# 464421_22-01_01_Sheet1.net
KiCad netlist of a schematic drawn in Altium Designer
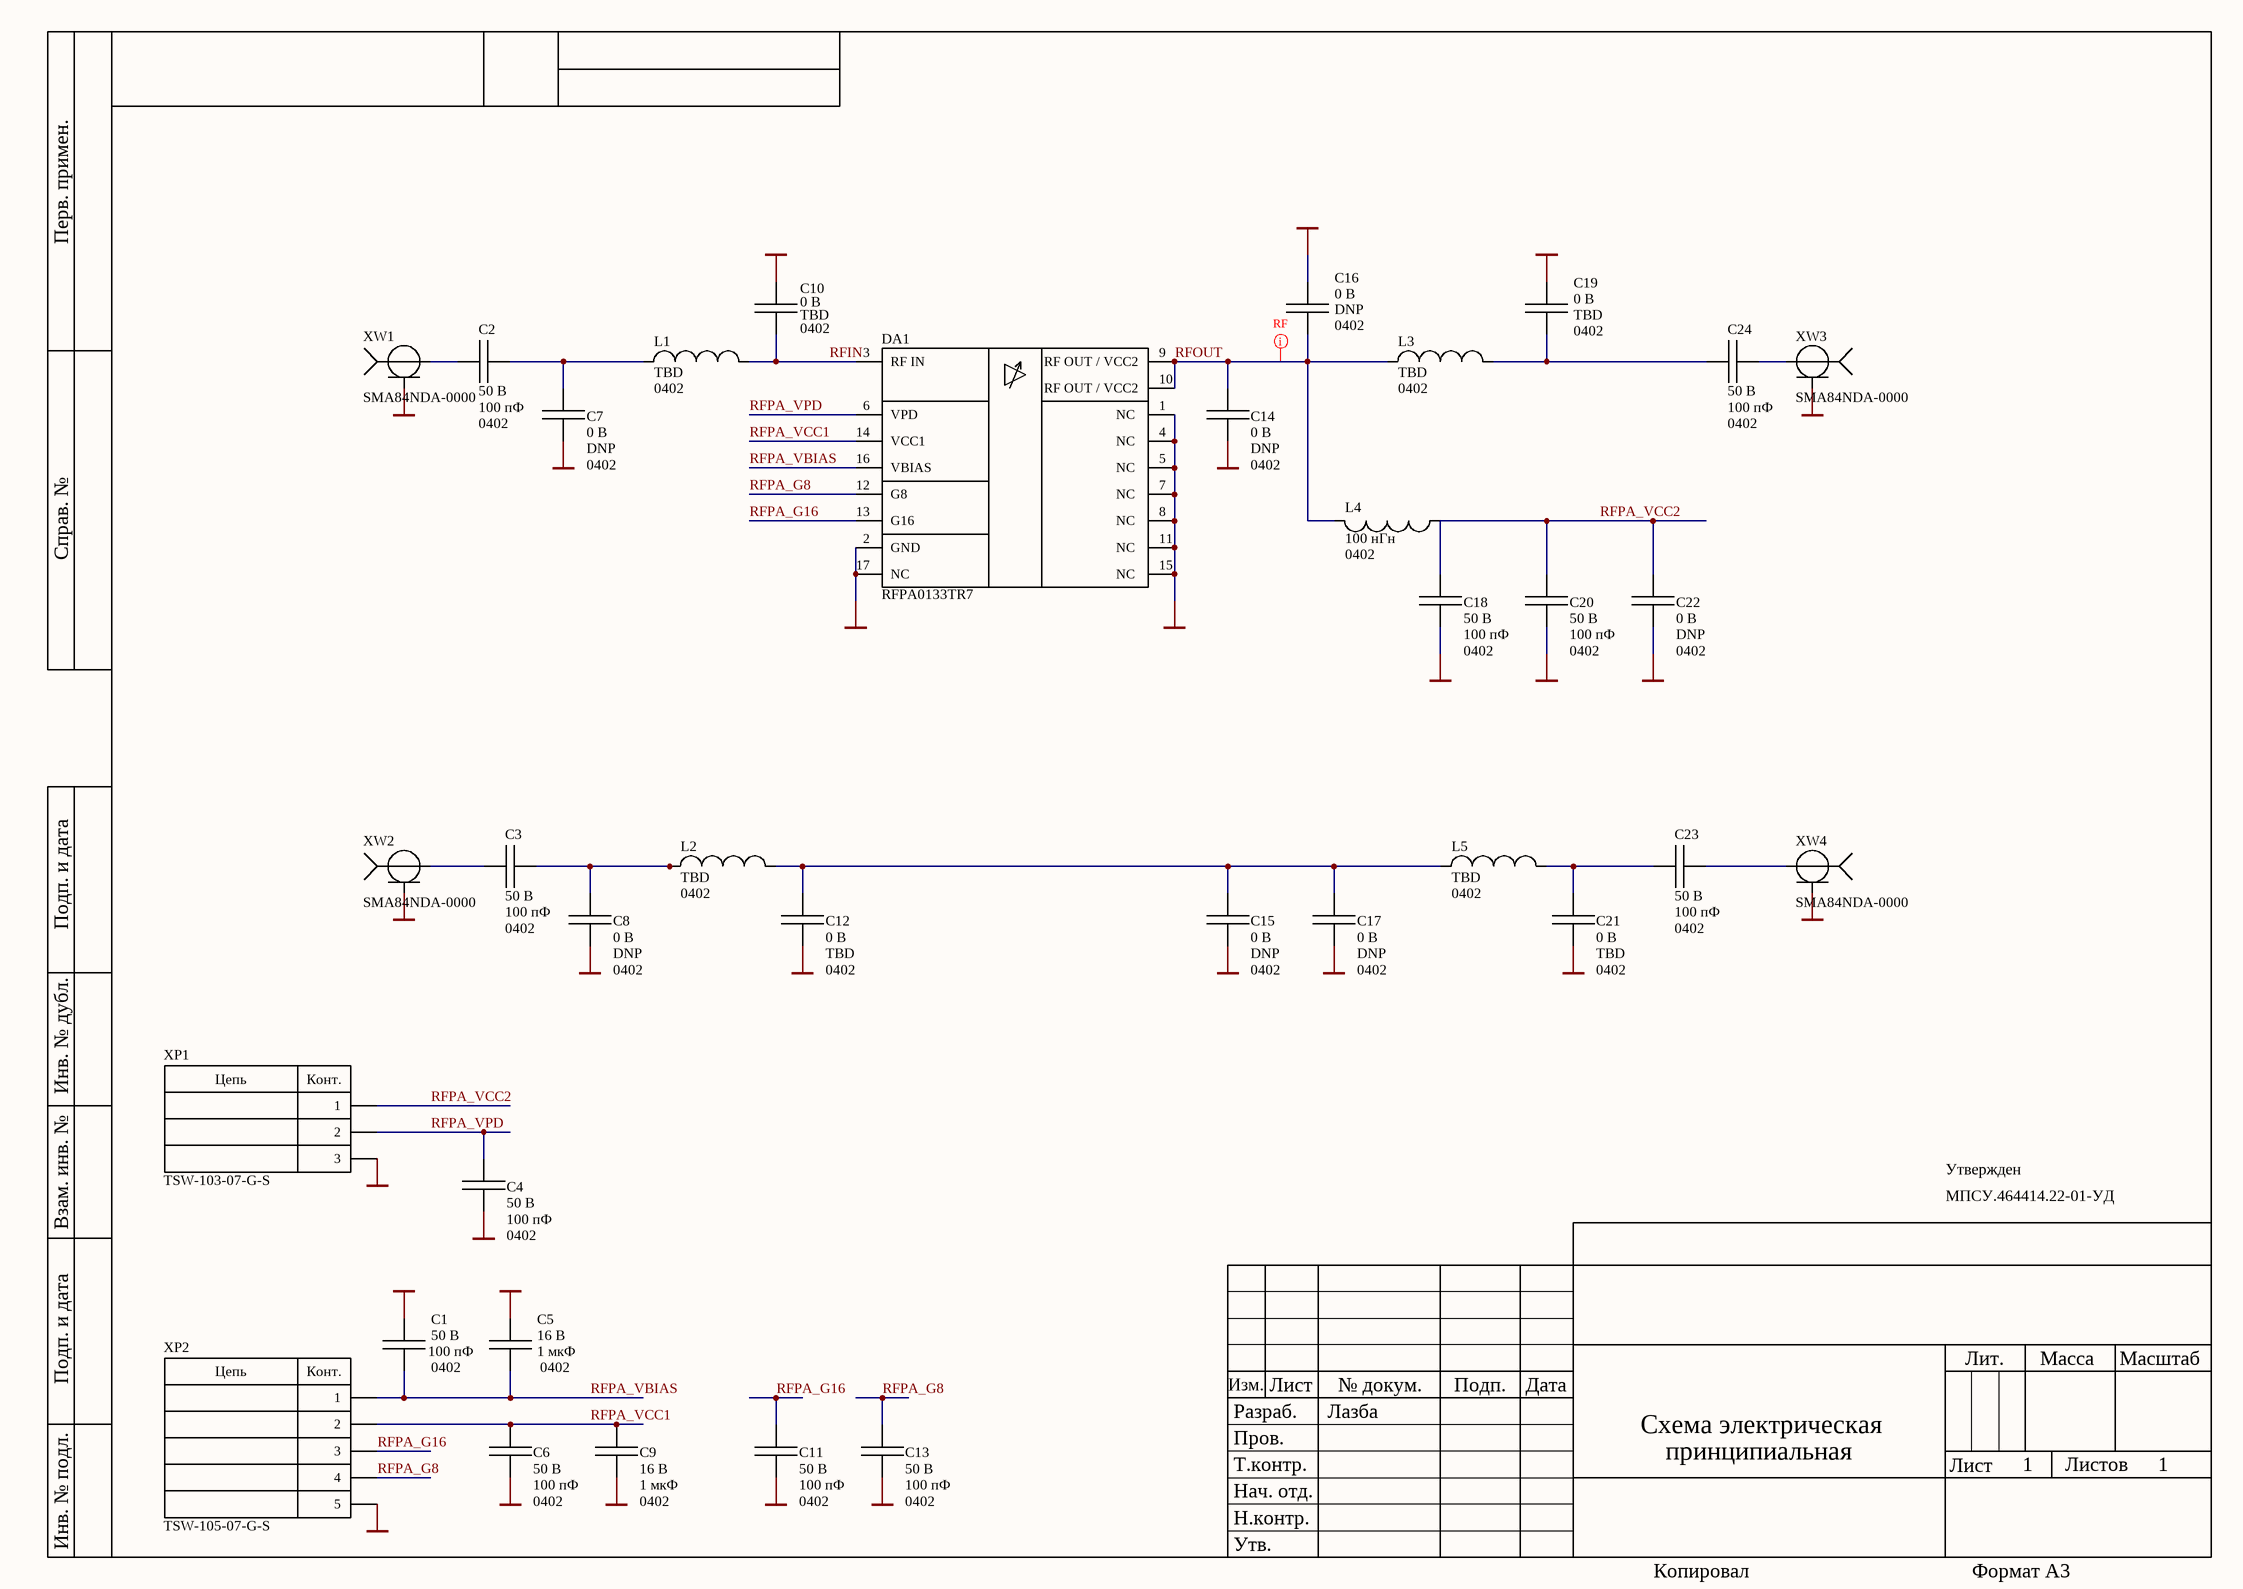
[diagram p0: МПСУ.464421.22-01.01 Sheet1.SchDoc]

(export (version "E")
  (design (tool "Eeschema 10.0.6"))
  (components
    (comp (ref "C1")
      (value "100 пФ")
      (footprint "Passive_V2_0:CAPC100X50X55L20N")
      (description "Capacitor 0402")
      (fields
        (field (name "PARTNUMBER") "GRM1555C1H101JZ01D")
        (field (name "MANUFACTURER") "Murata")
        (field (name "PEAK_CONDITION") "50 В")
        (field (name "PACKAGE") "0402")
        (field (name "DESIGNER") "Свидерский")
      )
      (libsource (lib "Passive_V2_0") (part "C 0402"))
    )
    (comp (ref "C2")
      (value "100 пФ")
      (footprint "Passive_V2_0:CAPC100X50X55L20N")
      (description "Capacitor 0402")
      (fields
        (field (name "PARTNUMBER") "GRM1555C1H101JZ01D")
        (field (name "MANUFACTURER") "Murata")
        (field (name "PEAK_CONDITION") "50 В")
        (field (name "PACKAGE") "0402")
        (field (name "DESIGNER") "Свидерский")
      )
      (libsource (lib "Passive_V2_0") (part "C 0402"))
    )
    (comp (ref "C3")
      (value "100 пФ")
      (footprint "Passive_V2_0:CAPC100X50X55L20N")
      (description "Capacitor 0402")
      (fields
        (field (name "PARTNUMBER") "GRM1555C1H101JZ01D")
        (field (name "MANUFACTURER") "Murata")
        (field (name "PEAK_CONDITION") "50 В")
        (field (name "PACKAGE") "0402")
        (field (name "DESIGNER") "Свидерский")
      )
      (libsource (lib "Passive_V2_0") (part "C 0402"))
    )
    (comp (ref "C4")
      (value "100 пФ")
      (footprint "Passive_V2_0:CAPC100X50X55L20N")
      (description "Capacitor 0402")
      (fields
        (field (name "PARTNUMBER") "GRM1555C1H101JZ01D")
        (field (name "MANUFACTURER") "Murata")
        (field (name "PEAK_CONDITION") "50 В")
        (field (name "PACKAGE") "0402")
        (field (name "DESIGNER") "Свидерский")
      )
      (libsource (lib "Passive_V2_0") (part "C 0402"))
    )
    (comp (ref "C5")
      (value "1 мкФ")
      (footprint "Passive_V2_0:CAPC100X50X55L20N")
      (description "Capacitor 0402")
      (fields
        (field (name "PARTNUMBER") "GRM155R61C105KA12D")
        (field (name "MANUFACTURER") "Murata")
        (field (name "PEAK_CONDITION") "16 В")
        (field (name "PACKAGE") "0402")
        (field (name "DESIGNER") "Свидерский")
      )
      (libsource (lib "Passive_V2_0") (part "C 0402"))
    )
    (comp (ref "C6")
      (value "100 пФ")
      (footprint "Passive_V2_0:CAPC100X50X55L20N")
      (description "Capacitor 0402")
      (fields
        (field (name "PARTNUMBER") "GRM1555C1H101JZ01D")
        (field (name "MANUFACTURER") "Murata")
        (field (name "PEAK_CONDITION") "50 В")
        (field (name "PACKAGE") "0402")
        (field (name "DESIGNER") "Свидерский")
      )
      (libsource (lib "Passive_V2_0") (part "C 0402"))
    )
    (comp (ref "C7")
      (value "DNP")
      (footprint "Passive_V2_0:CAPC100X50X55L20N")
      (description "Capacitor 0402")
      (fields
        (field (name "TOLERANCE") "0 %")
        (field (name "PEAK_CONDITION") "0 В")
        (field (name "PACKAGE") "0402")
        (field (name "Comment") "DNP 0402")
        (field (name "DESIGNER") "Свидерский")
      )
      (libsource (lib "Passive_V2_0") (part "C 0402"))
    )
    (comp (ref "C8")
      (value "DNP")
      (footprint "Passive_V2_0:CAPC100X50X55L20N")
      (description "Capacitor 0402")
      (fields
        (field (name "TOLERANCE") "0 %")
        (field (name "PEAK_CONDITION") "0 В")
        (field (name "PACKAGE") "0402")
        (field (name "Comment") "DNP 0402")
        (field (name "DESIGNER") "Свидерский")
      )
      (libsource (lib "Passive_V2_0") (part "C 0402"))
    )
    (comp (ref "C9")
      (value "1 мкФ")
      (footprint "Passive_V2_0:CAPC100X50X55L20N")
      (description "Capacitor 0402")
      (fields
        (field (name "PARTNUMBER") "GRM155R61C105KA12D")
        (field (name "MANUFACTURER") "Murata")
        (field (name "PEAK_CONDITION") "16 В")
        (field (name "PACKAGE") "0402")
        (field (name "DESIGNER") "Свидерский")
      )
      (libsource (lib "Passive_V2_0") (part "C 0402"))
    )
    (comp (ref "C10")
      (value "TBD")
      (footprint "Passive_V2_0:CAPC100X50X55L20N")
      (description "Capacitor 0402")
      (fields
        (field (name "TOLERANCE") "0 %")
        (field (name "PEAK_CONDITION") "0 В")
        (field (name "PACKAGE") "0402")
        (field (name "Comment") "TBD 0402")
        (field (name "DESIGNER") "Свидерский")
      )
      (libsource (lib "Passive_V2_0") (part "C 0402"))
    )
    (comp (ref "C11")
      (value "100 пФ")
      (footprint "Passive_V2_0:CAPC100X50X55L20N")
      (description "Capacitor 0402")
      (fields
        (field (name "PARTNUMBER") "GRM1555C1H101JZ01D")
        (field (name "MANUFACTURER") "Murata")
        (field (name "PEAK_CONDITION") "50 В")
        (field (name "PACKAGE") "0402")
        (field (name "DESIGNER") "Свидерский")
      )
      (libsource (lib "Passive_V2_0") (part "C 0402"))
    )
    (comp (ref "C12")
      (value "TBD")
      (footprint "Passive_V2_0:CAPC100X50X55L20N")
      (description "Capacitor 0402")
      (fields
        (field (name "TOLERANCE") "0 %")
        (field (name "PEAK_CONDITION") "0 В")
        (field (name "PACKAGE") "0402")
        (field (name "Comment") "TBD 0402")
        (field (name "DESIGNER") "Свидерский")
      )
      (libsource (lib "Passive_V2_0") (part "C 0402"))
    )
    (comp (ref "C13")
      (value "100 пФ")
      (footprint "Passive_V2_0:CAPC100X50X55L20N")
      (description "Capacitor 0402")
      (fields
        (field (name "PARTNUMBER") "GRM1555C1H101JZ01D")
        (field (name "MANUFACTURER") "Murata")
        (field (name "PEAK_CONDITION") "50 В")
        (field (name "PACKAGE") "0402")
        (field (name "DESIGNER") "Свидерский")
      )
      (libsource (lib "Passive_V2_0") (part "C 0402"))
    )
    (comp (ref "C14")
      (value "DNP")
      (footprint "Passive_V2_0:CAPC100X50X55L20N")
      (description "Capacitor 0402")
      (fields
        (field (name "TOLERANCE") "0 %")
        (field (name "PEAK_CONDITION") "0 В")
        (field (name "PACKAGE") "0402")
        (field (name "Comment") "DNP 0402")
        (field (name "DESIGNER") "Свидерский")
      )
      (libsource (lib "Passive_V2_0") (part "C 0402"))
    )
    (comp (ref "C15")
      (value "DNP")
      (footprint "Passive_V2_0:CAPC100X50X55L20N")
      (description "Capacitor 0402")
      (fields
        (field (name "TOLERANCE") "0 %")
        (field (name "PEAK_CONDITION") "0 В")
        (field (name "PACKAGE") "0402")
        (field (name "Comment") "DNP 0402")
        (field (name "DESIGNER") "Свидерский")
      )
      (libsource (lib "Passive_V2_0") (part "C 0402"))
    )
    (comp (ref "C16")
      (value "DNP")
      (footprint "Passive_V2_0:CAPC100X50X55L20N")
      (description "Capacitor 0402")
      (fields
        (field (name "TOLERANCE") "0 %")
        (field (name "PEAK_CONDITION") "0 В")
        (field (name "PACKAGE") "0402")
        (field (name "Comment") "DNP 0402")
        (field (name "DESIGNER") "Свидерский")
      )
      (libsource (lib "Passive_V2_0") (part "C 0402"))
    )
    (comp (ref "C17")
      (value "DNP")
      (footprint "Passive_V2_0:CAPC100X50X55L20N")
      (description "Capacitor 0402")
      (fields
        (field (name "TOLERANCE") "0 %")
        (field (name "PEAK_CONDITION") "0 В")
        (field (name "PACKAGE") "0402")
        (field (name "Comment") "DNP 0402")
        (field (name "DESIGNER") "Свидерский")
      )
      (libsource (lib "Passive_V2_0") (part "C 0402"))
    )
    (comp (ref "C18")
      (value "100 пФ")
      (footprint "Passive_V2_0:CAPC100X50X55L20N")
      (description "Capacitor 0402")
      (fields
        (field (name "PARTNUMBER") "GRM1555C1H101JZ01D")
        (field (name "MANUFACTURER") "Murata")
        (field (name "PEAK_CONDITION") "50 В")
        (field (name "PACKAGE") "0402")
        (field (name "DESIGNER") "Свидерский")
      )
      (libsource (lib "Passive_V2_0") (part "C 0402"))
    )
    (comp (ref "C19")
      (value "TBD")
      (footprint "Passive_V2_0:CAPC100X50X55L20N")
      (description "Capacitor 0402")
      (fields
        (field (name "TOLERANCE") "0 %")
        (field (name "PEAK_CONDITION") "0 В")
        (field (name "PACKAGE") "0402")
        (field (name "Comment") "TBD 0402")
        (field (name "DESIGNER") "Свидерский")
      )
      (libsource (lib "Passive_V2_0") (part "C 0402"))
    )
    (comp (ref "C20")
      (value "100 пФ")
      (footprint "Passive_V2_0:CAPC100X50X55L20N")
      (description "Capacitor 0402")
      (fields
        (field (name "PARTNUMBER") "GRM1555C1H101JZ01D")
        (field (name "MANUFACTURER") "Murata")
        (field (name "PEAK_CONDITION") "50 В")
        (field (name "PACKAGE") "0402")
        (field (name "DESIGNER") "Свидерский")
      )
      (libsource (lib "Passive_V2_0") (part "C 0402"))
    )
    (comp (ref "C21")
      (value "TBD")
      (footprint "Passive_V2_0:CAPC100X50X55L20N")
      (description "Capacitor 0402")
      (fields
        (field (name "TOLERANCE") "0 %")
        (field (name "PEAK_CONDITION") "0 В")
        (field (name "PACKAGE") "0402")
        (field (name "Comment") "TBD 0402")
        (field (name "DESIGNER") "Свидерский")
      )
      (libsource (lib "Passive_V2_0") (part "C 0402"))
    )
    (comp (ref "C22")
      (value "DNP")
      (footprint "Passive_V2_0:CAPC100X50X55L20N")
      (description "Capacitor 0402")
      (fields
        (field (name "TOLERANCE") "0 %")
        (field (name "PEAK_CONDITION") "0 В")
        (field (name "PACKAGE") "0402")
        (field (name "Comment") "DNP 0402")
        (field (name "DESIGNER") "Свидерский")
      )
      (libsource (lib "Passive_V2_0") (part "C 0402"))
    )
    (comp (ref "C23")
      (value "100 пФ")
      (footprint "Passive_V2_0:CAPC100X50X55L20N")
      (description "Capacitor 0402")
      (fields
        (field (name "PARTNUMBER") "GRM1555C1H101JZ01D")
        (field (name "MANUFACTURER") "Murata")
        (field (name "PEAK_CONDITION") "50 В")
        (field (name "PACKAGE") "0402")
        (field (name "DESIGNER") "Свидерский")
      )
      (libsource (lib "Passive_V2_0") (part "C 0402"))
    )
    (comp (ref "C24")
      (value "100 пФ")
      (footprint "Passive_V2_0:CAPC100X50X55L20N")
      (description "Capacitor 0402")
      (fields
        (field (name "PARTNUMBER") "GRM1555C1H101JZ01D")
        (field (name "MANUFACTURER") "Murata")
        (field (name "PEAK_CONDITION") "50 В")
        (field (name "PACKAGE") "0402")
        (field (name "DESIGNER") "Свидерский")
      )
      (libsource (lib "Passive_V2_0") (part "C 0402"))
    )
    (comp (ref "DA1")
      (value "RFPA0133TR7")
      (footprint "IC_V2_0:QFN50P300X300X90_HS-17N")
      (description "380 to 960 MHz, 3 to 5V programmable gain high efficiency power amplifier")
      (fields
        (field (name "MANUFACTURER") "RFD, Qorvo")
        (field (name "PARTNUMBER") "RFPA0133TR7")
        (field (name "DESIGNER") "Лазба")
      )
      (libsource (lib "IC_V2_0") (part "RFPA0133TR7"))
    )
    (comp (ref "L1")
      (value "TBD")
      (footprint "Passive_V2_0:INDC100X50X60L10N")
      (description "Inductor 0402")
      (fields
        (field (name "TOLERANCE") "0 %")
        (field (name "PACKAGE") "0402")
        (field (name "Comment") "TBD 0402")
        (field (name "DESIGNER") "Свидерский")
      )
      (libsource (lib "Passive_V2_0") (part "L 0402"))
    )
    (comp (ref "L2")
      (value "TBD")
      (footprint "Passive_V2_0:INDC100X50X60L10N")
      (description "Inductor 0402")
      (fields
        (field (name "TOLERANCE") "0 %")
        (field (name "PACKAGE") "0402")
        (field (name "Comment") "TBD 0402")
        (field (name "DESIGNER") "Свидерский")
      )
      (libsource (lib "Passive_V2_0") (part "L 0402"))
    )
    (comp (ref "L3")
      (value "TBD")
      (footprint "Passive_V2_0:INDC100X50X60L10N")
      (description "Inductor 0402")
      (fields
        (field (name "TOLERANCE") "0 %")
        (field (name "PACKAGE") "0402")
        (field (name "Comment") "TBD 0402")
        (field (name "DESIGNER") "Свидерский")
      )
      (libsource (lib "Passive_V2_0") (part "L 0402"))
    )
    (comp (ref "L4")
      (value "100 нГн")
      (footprint "Passive_V2_0:INDC100X50X60L10N")
      (description "Inductor 0402")
      (fields
        (field (name "PARTNUMBER") "LQG15HNR10J02D")
        (field (name "TOLERANCE") "5 %")
        (field (name "PACKAGE") "0402")
        (field (name "DESIGNER") "Свидерский")
      )
      (libsource (lib "Passive_V2_0") (part "L 0402"))
    )
    (comp (ref "L5")
      (value "TBD")
      (footprint "Passive_V2_0:INDC100X50X60L10N")
      (description "Inductor 0402")
      (fields
        (field (name "TOLERANCE") "0 %")
        (field (name "PACKAGE") "0402")
        (field (name "Comment") "TBD 0402")
        (field (name "DESIGNER") "Свидерский")
      )
      (libsource (lib "Passive_V2_0") (part "L 0402"))
    )
    (comp (ref "XP1")
      (value "TSW-103-07-G-S")
      (footprint "Connectors_V2_0:TSW-103-07-G-S")
      (description "Вилка 2,54 мм")
      (fields
        (field (name "MANUFACTURER") "Samtec")
        (field (name "PARTNUMBER") "TSW-103-07-G-S")
        (field (name "DESIGNER") "Затонская")
      )
      (libsource (lib "Connectors_V2_0") (part "TSW-103-07-G-S"))
    )
    (comp (ref "XP2")
      (value "TSW-105-07-G-S")
      (footprint "Connectors_V2_0:TSW-105-07-G-S")
      (description "Вилка 2,54 мм")
      (fields
        (field (name "MANUFACTURER") "Samtec")
        (field (name "PARTNUMBER") "TSW-105-07-G-S")
        (field (name "DESIGNER") "Затонская")
      )
      (libsource (lib "Connectors_V2_0") (part "TSW-105-07-G-S"))
    )
    (comp (ref "XW1")
      (value "SMA84NDA-0000")
      (footprint "Connectors_V2_0:SMA84NDA-0000")
      (description "SMA Jack P.C.B Mount (End Launch) 50 Ohm")
      (fields
        (field (name "MANUFACTURER") "Jyebao")
        (field (name "PARTNUMBER") "SMA84NDA-0000")
        (field (name "DESIGNER") "Карпов")
      )
      (libsource (lib "Connectors_V2_0") (part "SMA84NDA-0000"))
    )
    (comp (ref "XW2")
      (value "SMA84NDA-0000")
      (footprint "Connectors_V2_0:SMA84NDA-0000")
      (description "SMA Jack P.C.B Mount (End Launch) 50 Ohm")
      (fields
        (field (name "MANUFACTURER") "Jyebao")
        (field (name "PARTNUMBER") "SMA84NDA-0000")
        (field (name "DESIGNER") "Карпов")
      )
      (libsource (lib "Connectors_V2_0") (part "SMA84NDA-0000"))
    )
    (comp (ref "XW3")
      (value "SMA84NDA-0000")
      (footprint "Connectors_V2_0:SMA84NDA-0000")
      (description "SMA Jack P.C.B Mount (End Launch) 50 Ohm")
      (fields
        (field (name "MANUFACTURER") "Jyebao")
        (field (name "PARTNUMBER") "SMA84NDA-0000")
        (field (name "DESIGNER") "Карпов")
      )
      (libsource (lib "Connectors_V2_0") (part "SMA84NDA-0000"))
    )
    (comp (ref "XW4")
      (value "SMA84NDA-0000")
      (footprint "Connectors_V2_0:SMA84NDA-0000")
      (description "SMA Jack P.C.B Mount (End Launch) 50 Ohm")
      (fields
        (field (name "MANUFACTURER") "Jyebao")
        (field (name "PARTNUMBER") "SMA84NDA-0000")
        (field (name "DESIGNER") "Карпов")
      )
      (libsource (lib "Connectors_V2_0") (part "SMA84NDA-0000"))
    )
  )
  (nets
    (net (code "2") (name "/RFIN") (class "Default")
      (node (ref "C10") (pin "1") (pinfunction "1_1") (pintype "passive"))
      (node (ref "DA1") (pin "3") (pinfunction "RF_IN_3") (pintype "passive"))
      (node (ref "L1") (pin "2") (pinfunction "2_2") (pintype "passive"))
    )
    (net (code "3") (name "/RFOUT") (class "Default")
      (node (ref "C14") (pin "1") (pinfunction "1_1") (pintype "passive"))
      (node (ref "C16") (pin "2") (pinfunction "2_2") (pintype "passive"))
      (node (ref "DA1") (pin "10") (pinfunction "RF_OUT_/_VCC2_10") (pintype "passive"))
      (node (ref "DA1") (pin "9") (pinfunction "RF_OUT_/_VCC2_9") (pintype "passive"))
      (node (ref "L3") (pin "1") (pinfunction "1_1") (pintype "passive"))
      (node (ref "L4") (pin "2") (pinfunction "2_2") (pintype "passive"))
    )
    (net (code "4") (name "/RFPA_G8") (class "Default")
      (node (ref "C13") (pin "2") (pinfunction "2_2") (pintype "passive"))
      (node (ref "DA1") (pin "12") (pinfunction "G8_12") (pintype "passive"))
      (node (ref "XP2") (pin "4") (pinfunction "4_4") (pintype "passive"))
    )
    (net (code "5") (name "/RFPA_G16") (class "Default")
      (node (ref "C11") (pin "2") (pinfunction "2_2") (pintype "passive"))
      (node (ref "DA1") (pin "13") (pinfunction "G16_13") (pintype "passive"))
      (node (ref "XP2") (pin "3") (pinfunction "3_3") (pintype "passive"))
    )
    (net (code "6") (name "/RFPA_VBIAS") (class "Default")
      (node (ref "C1") (pin "2") (pinfunction "2_2") (pintype "passive"))
      (node (ref "C5") (pin "2") (pinfunction "2_2") (pintype "passive"))
      (node (ref "DA1") (pin "16") (pinfunction "VBIAS_16") (pintype "passive"))
      (node (ref "XP2") (pin "1") (pinfunction "1_1") (pintype "passive"))
    )
    (net (code "7") (name "/RFPA_VCC2") (class "Default")
      (node (ref "C18") (pin "1") (pinfunction "1_1") (pintype "passive"))
      (node (ref "C20") (pin "1") (pinfunction "1_1") (pintype "passive"))
      (node (ref "C22") (pin "1") (pinfunction "1_1") (pintype "passive"))
      (node (ref "L4") (pin "1") (pinfunction "1_1") (pintype "passive"))
      (node (ref "XP1") (pin "1") (pinfunction "1_1") (pintype "passive"))
    )
    (net (code "8") (name "/RFPA_VPD") (class "Default")
      (node (ref "C4") (pin "2") (pinfunction "2_2") (pintype "passive"))
      (node (ref "DA1") (pin "6") (pinfunction "VPD_6") (pintype "passive"))
      (node (ref "XP1") (pin "2") (pinfunction "2_2") (pintype "passive"))
    )
    (net (code "9") (name "/RFPA_VСС1") (class "Default")
      (node (ref "C6") (pin "2") (pinfunction "2_2") (pintype "passive"))
      (node (ref "C9") (pin "2") (pinfunction "2_2") (pintype "passive"))
      (node (ref "DA1") (pin "14") (pinfunction "VCC1_14") (pintype "passive"))
      (node (ref "XP2") (pin "2") (pinfunction "2_2") (pintype "passive"))
    )
    (net (code "10") (name "GND") (class "Default")
      (node (ref "C1") (pin "1") (pinfunction "1_1") (pintype "passive"))
      (node (ref "C10") (pin "2") (pinfunction "2_2") (pintype "passive"))
      (node (ref "C11") (pin "1") (pinfunction "1_1") (pintype "passive"))
      (node (ref "C12") (pin "2") (pinfunction "2_2") (pintype "passive"))
      (node (ref "C13") (pin "1") (pinfunction "1_1") (pintype "passive"))
      (node (ref "C14") (pin "2") (pinfunction "2_2") (pintype "passive"))
      (node (ref "C15") (pin "1") (pinfunction "1_1") (pintype "passive"))
      (node (ref "C16") (pin "1") (pinfunction "1_1") (pintype "passive"))
      (node (ref "C17") (pin "2") (pinfunction "2_2") (pintype "passive"))
      (node (ref "C18") (pin "2") (pinfunction "2_2") (pintype "passive"))
      (node (ref "C19") (pin "2") (pinfunction "2_2") (pintype "passive"))
      (node (ref "C20") (pin "2") (pinfunction "2_2") (pintype "passive"))
      (node (ref "C21") (pin "2") (pinfunction "2_2") (pintype "passive"))
      (node (ref "C22") (pin "2") (pinfunction "2_2") (pintype "passive"))
      (node (ref "C4") (pin "1") (pinfunction "1_1") (pintype "passive"))
      (node (ref "C5") (pin "1") (pinfunction "1_1") (pintype "passive"))
      (node (ref "C6") (pin "1") (pinfunction "1_1") (pintype "passive"))
      (node (ref "C7") (pin "2") (pinfunction "2_2") (pintype "passive"))
      (node (ref "C8") (pin "2") (pinfunction "2_2") (pintype "passive"))
      (node (ref "C9") (pin "1") (pinfunction "1_1") (pintype "passive"))
      (node (ref "DA1") (pin "1") (pinfunction "NC_1") (pintype "passive"))
      (node (ref "DA1") (pin "11") (pinfunction "NC_11") (pintype "passive"))
      (node (ref "DA1") (pin "15") (pinfunction "NC_15") (pintype "passive"))
      (node (ref "DA1") (pin "17") (pinfunction "NC_17") (pintype "passive"))
      (node (ref "DA1") (pin "2") (pinfunction "GND_2") (pintype "passive"))
      (node (ref "DA1") (pin "4") (pinfunction "NC_4") (pintype "passive"))
      (node (ref "DA1") (pin "5") (pinfunction "NC_5") (pintype "passive"))
      (node (ref "DA1") (pin "7") (pinfunction "NC_7") (pintype "passive"))
      (node (ref "DA1") (pin "8") (pinfunction "NC_8") (pintype "passive"))
      (node (ref "XP1") (pin "3") (pinfunction "3_3") (pintype "passive"))
      (node (ref "XP2") (pin "5") (pinfunction "5_5") (pintype "passive"))
      (node (ref "XW1") (pin "2") (pinfunction "GND_2") (pintype "passive"))
      (node (ref "XW2") (pin "2") (pinfunction "GND_2") (pintype "passive"))
      (node (ref "XW3") (pin "2") (pinfunction "GND_2") (pintype "passive"))
      (node (ref "XW4") (pin "2") (pinfunction "GND_2") (pintype "passive"))
    )
    (net (code "11") (name "Net-(C2-Pad2)") (class "Default")
      (node (ref "C2") (pin "2") (pinfunction "2_2") (pintype "passive"))
      (node (ref "C7") (pin "1") (pinfunction "1_1") (pintype "passive"))
      (node (ref "L1") (pin "1") (pinfunction "1_1") (pintype "passive"))
    )
    (net (code "12") (name "Net-(C3-Pad2)") (class "Default")
      (node (ref "C3") (pin "2") (pinfunction "2_2") (pintype "passive"))
      (node (ref "C8") (pin "1") (pinfunction "1_1") (pintype "passive"))
      (node (ref "L2") (pin "1") (pinfunction "1_1") (pintype "passive"))
    )
    (net (code "13") (name "Net-(C12-Pad1)") (class "Default")
      (node (ref "C12") (pin "1") (pinfunction "1_1") (pintype "passive"))
      (node (ref "C15") (pin "2") (pinfunction "2_2") (pintype "passive"))
      (node (ref "C17") (pin "1") (pinfunction "1_1") (pintype "passive"))
      (node (ref "L2") (pin "2") (pinfunction "2_2") (pintype "passive"))
      (node (ref "L5") (pin "1") (pinfunction "1_1") (pintype "passive"))
    )
    (net (code "14") (name "Net-(C19-Pad1)") (class "Default")
      (node (ref "C19") (pin "1") (pinfunction "1_1") (pintype "passive"))
      (node (ref "C24") (pin "1") (pinfunction "1_1") (pintype "passive"))
      (node (ref "L3") (pin "2") (pinfunction "2_2") (pintype "passive"))
    )
    (net (code "15") (name "Net-(C21-Pad1)") (class "Default")
      (node (ref "C21") (pin "1") (pinfunction "1_1") (pintype "passive"))
      (node (ref "C23") (pin "1") (pinfunction "1_1") (pintype "passive"))
      (node (ref "L5") (pin "2") (pinfunction "2_2") (pintype "passive"))
    )
    (net (code "16") (name "Net-(XW1-RF)") (class "Default")
      (node (ref "C2") (pin "1") (pinfunction "1_1") (pintype "passive"))
      (node (ref "XW1") (pin "1") (pinfunction "RF_1") (pintype "passive"))
    )
    (net (code "17") (name "Net-(XW2-RF)") (class "Default")
      (node (ref "C3") (pin "1") (pinfunction "1_1") (pintype "passive"))
      (node (ref "XW2") (pin "1") (pinfunction "RF_1") (pintype "passive"))
    )
    (net (code "18") (name "Net-(XW3-RF)") (class "Default")
      (node (ref "C24") (pin "2") (pinfunction "2_2") (pintype "passive"))
      (node (ref "XW3") (pin "1") (pinfunction "RF_1") (pintype "passive"))
    )
    (net (code "19") (name "Net-(XW4-RF)") (class "Default")
      (node (ref "C23") (pin "2") (pinfunction "2_2") (pintype "passive"))
      (node (ref "XW4") (pin "1") (pinfunction "RF_1") (pintype "passive"))
    )
  )
)
